# Schematic.net
KiCad netlist of a schematic drawn in Altium Designer
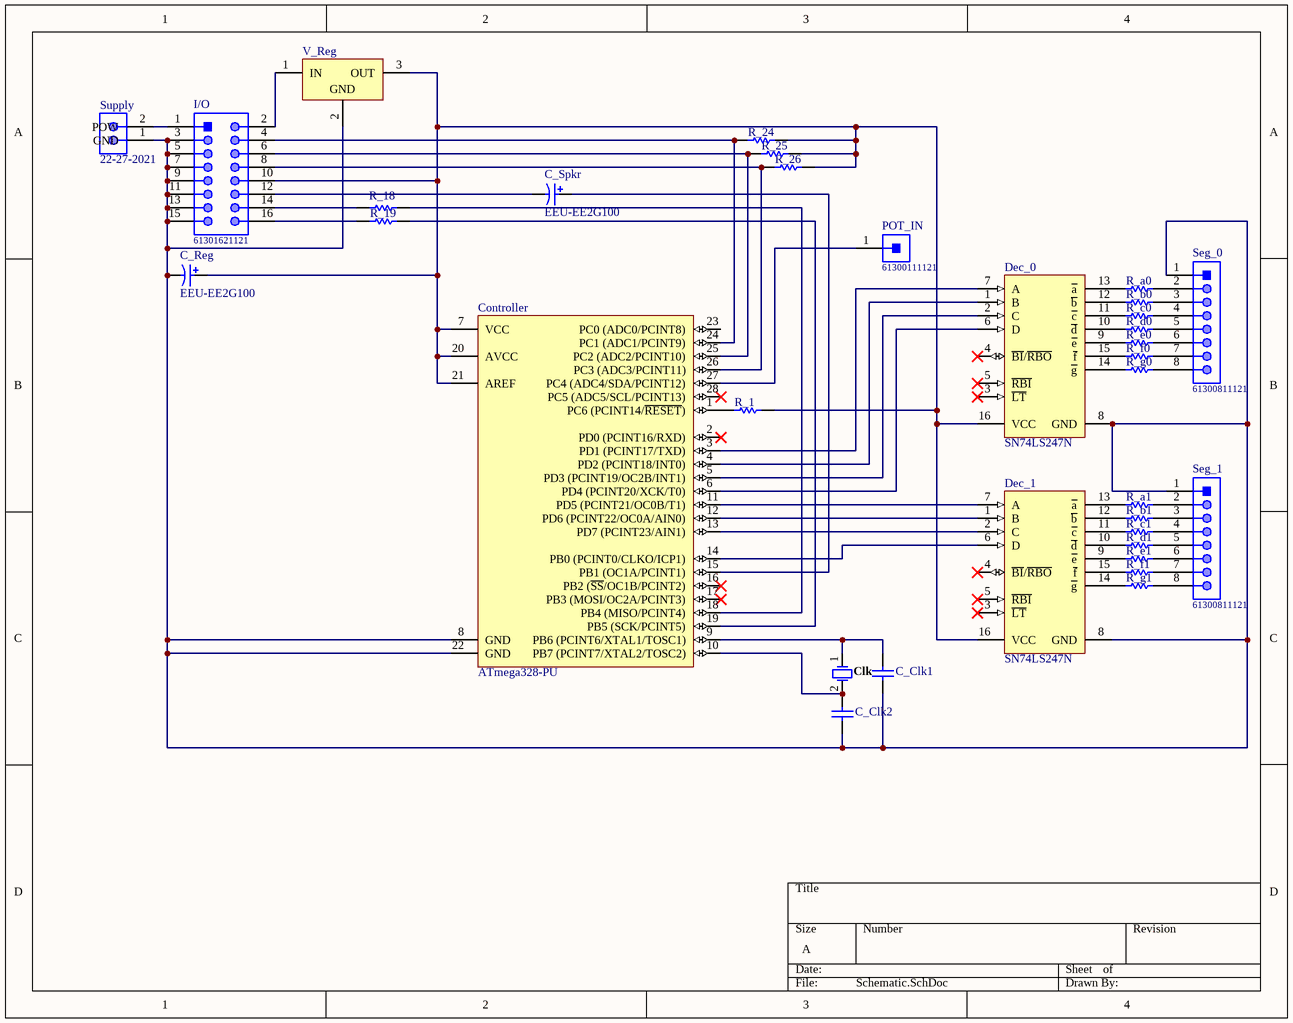
[diagram p0: Schematic.SchDoc]

(export (version "E")
  (design (tool "Eeschema 10.0.6"))
  (components
    (comp (ref "Clk")
      (value "FOXSLF/120-20")
      (footprint "FOX-FOXSLF-2_V")
      (description "Resistance Weld Thru-Hole Crystal, 12 MHz, +/-30 ppm, -20 to 70 degC, 2-Pin THD, RoHS, Bulk")
      (libsource (lib "Altium Content Vault") (part "XTAL-1-2-2"))
    )
    (comp (ref "Controller")
      (value "ATmega328-PU")
      (footprint "28P3")
      (libsource (lib "Altium Content Vault") (part "MC-8B-ATM48-IL28"))
    )
    (comp (ref "C_Clk1")
      (value "C315C220K1G5TA")
      (footprint "KEMT-C315-THT-2")
      (description "Capacitor, Ceramic, 22 pF, +/-10 %, 100 V, -55 to 125 degC, 2-Pin THD, RoHS, Bulk")
      (libsource (lib "Altium Content Vault") (part "CAP-NP-2"))
    )
    (comp (ref "C_Clk2")
      (value "C315C220K1G5TA")
      (footprint "KEMT-C315-THT-2")
      (description "Capacitor, Ceramic, 22 pF, +/-10 %, 100 V, -55 to 125 degC, 2-Pin THD, RoHS, Bulk")
      (libsource (lib "Altium Content Vault") (part "CAP-NP-2"))
    )
    (comp (ref "C_Reg")
      (value "EEU-EE2G100")
      (footprint "PNSC-EEU-EE2G100-2_V")
      (fields (field (name "MANUFACTURER") "Panasonic"))
      (libsource (lib "Altium Content Vault") (part "PNSC-CAP-P-2"))
    )
    (comp (ref "C_Spkr")
      (value "EEU-EE2G100")
      (footprint "PNSC-EEU-EE2G100-2_V")
      (fields (field (name "MANUFACTURER") "Panasonic"))
      (libsource (lib "Altium Content Vault") (part "PNSC-CAP-P-2"))
    )
    (comp (ref "Dec_0")
      (value "SN74LS247N")
      (footprint "N0016A")
      (description "BCD-to-7-Segment Decoder / Driver, 4.75 to 5.25 V, 0 to 70 degC, 16-pin DIP (N16), Pb-Free (RoHS)")
      (fields (field (name "MANUFACTURER") "Texas Instruments"))
      (libsource (lib "Altium Content Vault") (part "TI-SNX4XX247-16"))
    )
    (comp (ref "Dec_1")
      (value "SN74LS247N")
      (footprint "N0016A")
      (description "BCD-to-7-Segment Decoder / Driver, 4.75 to 5.25 V, 0 to 70 degC, 16-pin DIP (N16), Pb-Free (RoHS)")
      (fields (field (name "MANUFACTURER") "Texas Instruments"))
      (libsource (lib "Altium Content Vault") (part "TI-SNX4XX247-16"))
    )
    (comp (ref "I/O")
      (value "61301621121")
      (footprint "61301621121")
      (description "THT Vertical Pin Header WR-PHD, Pitch 2.54 mm, Dual Row, 16 pins")
      (fields (field (name "MANUFACTURER") "Wurth Elektronik") (field (name "PUBLISHER") "WurthElektronik"))
      (libsource (lib "Altium Content Vault") (part "WE-CN-2P-M-R16"))
    )
    (comp (ref "POT_IN")
      (value "61300111121")
      (footprint "61300111121")
      (description "THT Vertical Pin Header WR-PHD, Pitch 2.54 mm, Single Row, 1 pins")
      (fields (field (name "MANUFACTURER") "Wurth Elektronik") (field (name "PUBLISHER") "WurthElektronik"))
      (libsource (lib "Altium Content Vault") (part "WE-CN-1P-M-R1"))
    )
    (comp (ref "R_1")
      (value "MFR-25FBF52-1K")
      (footprint "RESA60-630X240")
      (description "Axial Resistor, 1 KOhm, +/- 1%, 250 mW, -55 to 155 degC, 2-Pin THD, RoHS, Bulk")
      (fields (field (name "TOLERANCE") "1%"))
      (libsource (lib "Altium Content Vault") (part "RES-2"))
    )
    (comp (ref "R_18")
      (value "FR-25FF52-1K")
      (footprint "RESA60-630X240")
      (description "Axial Resistor, 1 KOhm, +/- 1%, 250 mW, -55 to 155 degC, 2-Pin THD, RoHS, Bulk")
      (fields (field (name "TOLERANCE") "1%"))
      (libsource (lib "Altium Content Vault") (part "RES-2"))
    )
    (comp (ref "R_19")
      (value "MFR-25FBF52-1K")
      (footprint "RESA60-630X240")
      (description "Axial Resistor, 1 KOhm, +/- 1%, 250 mW, -55 to 155 degC, 2-Pin THD, RoHS, Bulk")
      (fields (field (name "TOLERANCE") "1%"))
      (libsource (lib "Altium Content Vault") (part "RES-2"))
    )
    (comp (ref "R_24")
      (value "MFR-25FBF52-1K")
      (footprint "RESA60-630X240")
      (description "Axial Resistor, 1 KOhm, +/- 1%, 250 mW, -55 to 155 degC, 2-Pin THD, RoHS, Bulk")
      (fields (field (name "TOLERANCE") "1%"))
      (libsource (lib "Altium Content Vault") (part "RES-2"))
    )
    (comp (ref "R_25")
      (value "MFR-25FBF52-1K")
      (footprint "RESA60-630X240")
      (description "Axial Resistor, 1 KOhm, +/- 1%, 250 mW, -55 to 155 degC, 2-Pin THD, RoHS, Bulk")
      (fields (field (name "TOLERANCE") "1%"))
      (libsource (lib "Altium Content Vault") (part "RES-2"))
    )
    (comp (ref "R_26")
      (value "MFR-25FBF52-1K")
      (footprint "RESA60-630X240")
      (description "Axial Resistor, 1 KOhm, +/- 1%, 250 mW, -55 to 155 degC, 2-Pin THD, RoHS, Bulk")
      (fields (field (name "TOLERANCE") "1%"))
      (libsource (lib "Altium Content Vault") (part "RES-2"))
    )
    (comp (ref "R_a0")
      (value "MFR-25FBF52-1K")
      (footprint "RESA60-630X240")
      (description "Axial Resistor, 1 KOhm, +/- 1%, 250 mW, -55 to 155 degC, 2-Pin THD, RoHS, Bulk")
      (fields (field (name "TOLERANCE") "1%"))
      (libsource (lib "Altium Content Vault") (part "RES-2"))
    )
    (comp (ref "R_a1")
      (value "MFR-25FBF52-1K")
      (footprint "RESA60-630X240")
      (description "Axial Resistor, 1 KOhm, +/- 1%, 250 mW, -55 to 155 degC, 2-Pin THD, RoHS, Bulk")
      (fields (field (name "TOLERANCE") "1%"))
      (libsource (lib "Altium Content Vault") (part "RES-2"))
    )
    (comp (ref "R_b0")
      (value "MFR-25FBF52-1K")
      (footprint "RESA60-630X240")
      (description "Axial Resistor, 1 KOhm, +/- 1%, 250 mW, -55 to 155 degC, 2-Pin THD, RoHS, Bulk")
      (fields (field (name "TOLERANCE") "1%"))
      (libsource (lib "Altium Content Vault") (part "RES-2"))
    )
    (comp (ref "R_b1")
      (value "MFR-25FBF52-1K")
      (footprint "RESA60-630X240")
      (description "Axial Resistor, 1 KOhm, +/- 1%, 250 mW, -55 to 155 degC, 2-Pin THD, RoHS, Bulk")
      (fields (field (name "TOLERANCE") "1%"))
      (libsource (lib "Altium Content Vault") (part "RES-2"))
    )
    (comp (ref "R_c0")
      (value "MFR-25FBF52-1K")
      (footprint "RESA60-630X240")
      (description "Axial Resistor, 1 KOhm, +/- 1%, 250 mW, -55 to 155 degC, 2-Pin THD, RoHS, Bulk")
      (fields (field (name "TOLERANCE") "1%"))
      (libsource (lib "Altium Content Vault") (part "RES-2"))
    )
    (comp (ref "R_c1")
      (value "MFR-25FBF52-1K")
      (footprint "RESA60-630X240")
      (description "Axial Resistor, 1 KOhm, +/- 1%, 250 mW, -55 to 155 degC, 2-Pin THD, RoHS, Bulk")
      (fields (field (name "TOLERANCE") "1%"))
      (libsource (lib "Altium Content Vault") (part "RES-2"))
    )
    (comp (ref "R_d0")
      (value "MFR-25FBF52-1K")
      (footprint "RESA60-630X240")
      (description "Axial Resistor, 1 KOhm, +/- 1%, 250 mW, -55 to 155 degC, 2-Pin THD, RoHS, Bulk")
      (fields (field (name "TOLERANCE") "1%"))
      (libsource (lib "Altium Content Vault") (part "RES-2"))
    )
    (comp (ref "R_d1")
      (value "MFR-25FBF52-1K")
      (footprint "RESA60-630X240")
      (description "Axial Resistor, 1 KOhm, +/- 1%, 250 mW, -55 to 155 degC, 2-Pin THD, RoHS, Bulk")
      (fields (field (name "TOLERANCE") "1%"))
      (libsource (lib "Altium Content Vault") (part "RES-2"))
    )
    (comp (ref "R_e0")
      (value "MFR-25FBF52-1K")
      (footprint "RESA60-630X240")
      (description "Axial Resistor, 1 KOhm, +/- 1%, 250 mW, -55 to 155 degC, 2-Pin THD, RoHS, Bulk")
      (fields (field (name "TOLERANCE") "1%"))
      (libsource (lib "Altium Content Vault") (part "RES-2"))
    )
    (comp (ref "R_e1")
      (value "MFR-25FBF52-1K")
      (footprint "RESA60-630X240")
      (description "Axial Resistor, 1 KOhm, +/- 1%, 250 mW, -55 to 155 degC, 2-Pin THD, RoHS, Bulk")
      (fields (field (name "TOLERANCE") "1%"))
      (libsource (lib "Altium Content Vault") (part "RES-2"))
    )
    (comp (ref "R_f0")
      (value "MFR-25FBF52-1K")
      (footprint "RESA60-630X240")
      (description "Axial Resistor, 1 KOhm, +/- 1%, 250 mW, -55 to 155 degC, 2-Pin THD, RoHS, Bulk")
      (fields (field (name "TOLERANCE") "1%"))
      (libsource (lib "Altium Content Vault") (part "RES-2"))
    )
    (comp (ref "R_f1")
      (value "MFR-25FBF52-1K")
      (footprint "RESA60-630X240")
      (description "Axial Resistor, 1 KOhm, +/- 1%, 250 mW, -55 to 155 degC, 2-Pin THD, RoHS, Bulk")
      (fields (field (name "TOLERANCE") "1%"))
      (libsource (lib "Altium Content Vault") (part "RES-2"))
    )
    (comp (ref "R_g0")
      (value "MFR-25FBF52-1K")
      (footprint "RESA60-630X240")
      (description "Axial Resistor, 1 KOhm, +/- 1%, 250 mW, -55 to 155 degC, 2-Pin THD, RoHS, Bulk")
      (fields (field (name "TOLERANCE") "1%"))
      (libsource (lib "Altium Content Vault") (part "RES-2"))
    )
    (comp (ref "R_g1")
      (value "MFR-25FBF52-1K")
      (footprint "RESA60-630X240")
      (description "Axial Resistor, 1 KOhm, +/- 1%, 250 mW, -55 to 155 degC, 2-Pin THD, RoHS, Bulk")
      (fields (field (name "TOLERANCE") "1%"))
      (libsource (lib "Altium Content Vault") (part "RES-2"))
    )
    (comp (ref "Seg_0")
      (value "61300811121")
      (footprint "61300811121")
      (description "THT Vertical Pin Header WR-PHD, Pitch 2.54 mm, Single Row, 8 pins")
      (fields (field (name "MANUFACTURER") "Wurth Elektronik") (field (name "PUBLISHER") "WurthElektronik"))
      (libsource (lib "Altium Content Vault") (part "WE-CN-1P-M-R8"))
    )
    (comp (ref "Seg_1")
      (value "61300811121")
      (footprint "61300811121")
      (description "THT Vertical Pin Header WR-PHD, Pitch 2.54 mm, Single Row, 8 pins")
      (fields (field (name "MANUFACTURER") "Wurth Elektronik") (field (name "PUBLISHER") "WurthElektronik"))
      (libsource (lib "Altium Content Vault") (part "WE-CN-1P-M-R8"))
    )
    (comp (ref "Supply")
      (value "22-27-2021")
      (footprint "MOLX-22-27-2021_V")
      (fields (field (name "MANUFACTURER") "Molex") (field (name "PARTNUMBER") "0022272021"))
      (libsource (lib "Altium Content Vault") (part "CN-1P-M-R2"))
    )
    (comp (ref "V_Reg")
      (value "LM7805CT")
      (footprint "FAIR-TO-220-3")
      (description "Positive Voltage Regulator, 5 V, 1 A, -40 to 125 degC, 3-Pin TO-220, RoHS, Tube")
      (fields (field (name "MANUFACTURER") "FairchildSemiconductor"))
      (libsource (lib "Altium Content Vault") (part "FAIR-LM7805CT-TO220-3"))
    )
  )
  (nets
    (net (code "1") (name "Net-(C_Spkr-Pad2)") (class "Default")
      (node (ref "C_Spkr") (pin "2") (pinfunction "2_2") (pintype "passive"))
      (node (ref "I/O") (pin "12") (pinfunction "12_12") (pintype "passive"))
    )
    (net (code "2") (name "Net-(Controller-AREF)") (class "Default")
      (node (ref "C_Reg") (pin "1") (pinfunction "1_1") (pintype "passive"))
      (node (ref "Controller") (pin "20") (pinfunction "AVCC_20") (pintype "power_in"))
      (node (ref "Controller") (pin "21") (pinfunction "AREF_21") (pintype "power_in"))
      (node (ref "Controller") (pin "7") (pinfunction "VCC_7") (pintype "power_in"))
      (node (ref "Dec_0") (pin "16") (pinfunction "VCC_16") (pintype "power_in"))
      (node (ref "Dec_1") (pin "16") (pinfunction "VCC_16") (pintype "power_in"))
      (node (ref "I/O") (pin "10") (pinfunction "10_10") (pintype "passive"))
      (node (ref "R_1") (pin "2") (pinfunction "2_2") (pintype "passive"))
      (node (ref "R_24") (pin "2") (pinfunction "2_2") (pintype "passive"))
      (node (ref "R_25") (pin "2") (pinfunction "2_2") (pintype "passive"))
      (node (ref "R_26") (pin "2") (pinfunction "2_2") (pintype "passive"))
      (node (ref "V_Reg") (pin "3") (pinfunction "OUT_3") (pintype "power_in"))
    )
    (net (code "3") (name "Net-(Controller-PB0_(PCINT0{slash}CLKO{slash}ICP1))") (class "Default")
      (node (ref "Controller") (pin "14") (pinfunction "PB0_(PCINT0/CLKO/ICP1)_14") (pintype "bidirectional"))
      (node (ref "Dec_1") (pin "6") (pinfunction "D_6") (pintype "input"))
    )
    (net (code "4") (name "Net-(Controller-PB1_(OC1A{slash}PCINT1))") (class "Default")
      (node (ref "C_Spkr") (pin "1") (pinfunction "1_1") (pintype "passive"))
      (node (ref "Controller") (pin "15") (pinfunction "PB1_(OC1A/PCINT1)_15") (pintype "bidirectional"))
    )
    (net (code "5") (name "Net-(Controller-PB4_(MISO{slash}PCINT4))") (class "Default")
      (node (ref "Controller") (pin "18") (pinfunction "PB4_(MISO/PCINT4)_18") (pintype "bidirectional"))
      (node (ref "R_18") (pin "2") (pinfunction "2_2") (pintype "passive"))
    )
    (net (code "6") (name "Net-(Controller-PB5_(SCK{slash}PCINT5))") (class "Default")
      (node (ref "Controller") (pin "19") (pinfunction "PB5_(SCK/PCINT5)_19") (pintype "bidirectional"))
      (node (ref "R_19") (pin "2") (pinfunction "2_2") (pintype "passive"))
    )
    (net (code "7") (name "Net-(Controller-PB6_(PCINT6{slash}XTAL1{slash}TOSC1))") (class "Default")
      (node (ref "C_Clk1") (pin "2") (pinfunction "2_2") (pintype "passive"))
      (node (ref "Clk") (pin "1") (pinfunction "1_1") (pintype "passive"))
      (node (ref "Controller") (pin "9") (pinfunction "PB6_(PCINT6/XTAL1/TOSC1)_9") (pintype "bidirectional"))
    )
    (net (code "8") (name "Net-(Controller-PB7_(PCINT7{slash}XTAL2{slash}TOSC2))") (class "Default")
      (node (ref "C_Clk2") (pin "1") (pinfunction "1_1") (pintype "passive"))
      (node (ref "Clk") (pin "2") (pinfunction "2_2") (pintype "passive"))
      (node (ref "Controller") (pin "10") (pinfunction "PB7_(PCINT7/XTAL2/TOSC2)_10") (pintype "bidirectional"))
    )
    (net (code "9") (name "Net-(Controller-PC1_(ADC1{slash}PCINT9))") (class "Default")
      (node (ref "Controller") (pin "24") (pinfunction "PC1_(ADC1/PCINT9)_24") (pintype "bidirectional"))
      (node (ref "I/O") (pin "4") (pinfunction "4_4") (pintype "passive"))
      (node (ref "R_24") (pin "1") (pinfunction "1_1") (pintype "passive"))
    )
    (net (code "10") (name "Net-(Controller-PC2_(ADC2{slash}PCINT10))") (class "Default")
      (node (ref "Controller") (pin "25") (pinfunction "PC2_(ADC2/PCINT10)_25") (pintype "bidirectional"))
      (node (ref "I/O") (pin "6") (pinfunction "6_6") (pintype "passive"))
      (node (ref "R_25") (pin "1") (pinfunction "1_1") (pintype "passive"))
    )
    (net (code "11") (name "Net-(Controller-PC3_(ADC3{slash}PCINT11))") (class "Default")
      (node (ref "Controller") (pin "26") (pinfunction "PC3_(ADC3/PCINT11)_26") (pintype "bidirectional"))
      (node (ref "I/O") (pin "8") (pinfunction "8_8") (pintype "passive"))
      (node (ref "R_26") (pin "1") (pinfunction "1_1") (pintype "passive"))
    )
    (net (code "12") (name "Net-(Controller-PC4_(ADC4{slash}SDA{slash}PCINT12))") (class "Default")
      (node (ref "Controller") (pin "27") (pinfunction "PC4_(ADC4/SDA/PCINT12)_27") (pintype "bidirectional"))
      (node (ref "POT_IN") (pin "1") (pinfunction "1_1") (pintype "passive"))
    )
    (net (code "13") (name "Net-(Controller-PC6_(PCINT14{slash}~{RESET}))") (class "Default")
      (node (ref "Controller") (pin "1") (pinfunction "PC6_(PCINT14/~{RESET})_1") (pintype "bidirectional"))
      (node (ref "R_1") (pin "1") (pinfunction "1_1") (pintype "passive"))
    )
    (net (code "14") (name "Net-(Controller-PD1_(PCINT17{slash}TXD))") (class "Default")
      (node (ref "Controller") (pin "3") (pinfunction "PD1_(PCINT17/TXD)_3") (pintype "bidirectional"))
      (node (ref "Dec_0") (pin "7") (pinfunction "A_7") (pintype "input"))
    )
    (net (code "15") (name "Net-(Controller-PD2_(PCINT18{slash}INT0))") (class "Default")
      (node (ref "Controller") (pin "4") (pinfunction "PD2_(PCINT18/INT0)_4") (pintype "bidirectional"))
      (node (ref "Dec_0") (pin "1") (pinfunction "B_1") (pintype "input"))
    )
    (net (code "16") (name "Net-(Controller-PD3_(PCINT19{slash}OC2B{slash}INT1))") (class "Default")
      (node (ref "Controller") (pin "5") (pinfunction "PD3_(PCINT19/OC2B/INT1)_5") (pintype "bidirectional"))
      (node (ref "Dec_0") (pin "2") (pinfunction "C_2") (pintype "input"))
    )
    (net (code "17") (name "Net-(Controller-PD4_(PCINT20{slash}XCK{slash}T0))") (class "Default")
      (node (ref "Controller") (pin "6") (pinfunction "PD4_(PCINT20/XCK/T0)_6") (pintype "bidirectional"))
      (node (ref "Dec_0") (pin "6") (pinfunction "D_6") (pintype "input"))
    )
    (net (code "18") (name "Net-(Controller-PD5_(PCINT21{slash}OC0B{slash}T1))") (class "Default")
      (node (ref "Controller") (pin "11") (pinfunction "PD5_(PCINT21/OC0B/T1)_11") (pintype "bidirectional"))
      (node (ref "Dec_1") (pin "7") (pinfunction "A_7") (pintype "input"))
    )
    (net (code "19") (name "Net-(Controller-PD6_(PCINT22{slash}OC0A{slash}AIN0))") (class "Default")
      (node (ref "Controller") (pin "12") (pinfunction "PD6_(PCINT22/OC0A/AIN0)_12") (pintype "bidirectional"))
      (node (ref "Dec_1") (pin "1") (pinfunction "B_1") (pintype "input"))
    )
    (net (code "20") (name "Net-(Controller-PD7_(PCINT23{slash}AIN1))") (class "Default")
      (node (ref "Controller") (pin "13") (pinfunction "PD7_(PCINT23/AIN1)_13") (pintype "bidirectional"))
      (node (ref "Dec_1") (pin "2") (pinfunction "C_2") (pintype "input"))
    )
    (net (code "21") (name "Net-(Dec_0-GND)") (class "Default")
      (node (ref "C_Clk1") (pin "1") (pinfunction "1_1") (pintype "passive"))
      (node (ref "C_Clk2") (pin "2") (pinfunction "2_2") (pintype "passive"))
      (node (ref "C_Reg") (pin "2") (pinfunction "2_2") (pintype "passive"))
      (node (ref "Controller") (pin "22") (pinfunction "GND_22") (pintype "power_in"))
      (node (ref "Controller") (pin "8") (pinfunction "GND_8") (pintype "power_in"))
      (node (ref "Dec_0") (pin "8") (pinfunction "GND_8") (pintype "power_in"))
      (node (ref "Dec_1") (pin "8") (pinfunction "GND_8") (pintype "power_in"))
      (node (ref "I/O") (pin "11") (pinfunction "11_11") (pintype "passive"))
      (node (ref "I/O") (pin "13") (pinfunction "13_13") (pintype "passive"))
      (node (ref "I/O") (pin "15") (pinfunction "15_15") (pintype "passive"))
      (node (ref "I/O") (pin "3") (pinfunction "3_3") (pintype "passive"))
      (node (ref "I/O") (pin "5") (pinfunction "5_5") (pintype "passive"))
      (node (ref "I/O") (pin "7") (pinfunction "7_7") (pintype "passive"))
      (node (ref "I/O") (pin "9") (pinfunction "9_9") (pintype "passive"))
      (node (ref "Seg_0") (pin "1") (pinfunction "1_1") (pintype "passive"))
      (node (ref "Seg_1") (pin "1") (pinfunction "1_1") (pintype "passive"))
      (node (ref "Supply") (pin "1") (pinfunction "GND_1") (pintype "passive"))
      (node (ref "V_Reg") (pin "2") (pinfunction "GND_2") (pintype "power_in"))
    )
    (net (code "22") (name "Net-(Dec_0-~{a})") (class "Default")
      (node (ref "Dec_0") (pin "13") (pinfunction "~{a}_13") (pintype "open_collector"))
      (node (ref "R_a0") (pin "1") (pinfunction "1_1") (pintype "passive"))
    )
    (net (code "23") (name "Net-(Dec_0-~{b})") (class "Default")
      (node (ref "Dec_0") (pin "12") (pinfunction "~{b}_12") (pintype "open_collector"))
      (node (ref "R_b0") (pin "1") (pinfunction "1_1") (pintype "passive"))
    )
    (net (code "24") (name "Net-(Dec_0-~{c})") (class "Default")
      (node (ref "Dec_0") (pin "11") (pinfunction "~{c}_11") (pintype "open_collector"))
      (node (ref "R_c0") (pin "1") (pinfunction "1_1") (pintype "passive"))
    )
    (net (code "25") (name "Net-(Dec_0-~{d})") (class "Default")
      (node (ref "Dec_0") (pin "10") (pinfunction "~{d}_10") (pintype "open_collector"))
      (node (ref "R_d0") (pin "1") (pinfunction "1_1") (pintype "passive"))
    )
    (net (code "26") (name "Net-(Dec_0-~{e})") (class "Default")
      (node (ref "Dec_0") (pin "9") (pinfunction "~{e}_9") (pintype "open_collector"))
      (node (ref "R_e0") (pin "1") (pinfunction "1_1") (pintype "passive"))
    )
    (net (code "27") (name "Net-(Dec_0-~{f})") (class "Default")
      (node (ref "Dec_0") (pin "15") (pinfunction "~{f}_15") (pintype "open_collector"))
      (node (ref "R_f0") (pin "1") (pinfunction "1_1") (pintype "passive"))
    )
    (net (code "28") (name "Net-(Dec_0-~{g})") (class "Default")
      (node (ref "Dec_0") (pin "14") (pinfunction "~{g}_14") (pintype "open_collector"))
      (node (ref "R_g0") (pin "1") (pinfunction "1_1") (pintype "passive"))
    )
    (net (code "29") (name "Net-(Dec_1-~{a})") (class "Default")
      (node (ref "Dec_1") (pin "13") (pinfunction "~{a}_13") (pintype "open_collector"))
      (node (ref "R_a1") (pin "1") (pinfunction "1_1") (pintype "passive"))
    )
    (net (code "30") (name "Net-(Dec_1-~{b})") (class "Default")
      (node (ref "Dec_1") (pin "12") (pinfunction "~{b}_12") (pintype "open_collector"))
      (node (ref "R_b1") (pin "1") (pinfunction "1_1") (pintype "passive"))
    )
    (net (code "31") (name "Net-(Dec_1-~{c})") (class "Default")
      (node (ref "Dec_1") (pin "11") (pinfunction "~{c}_11") (pintype "open_collector"))
      (node (ref "R_c1") (pin "1") (pinfunction "1_1") (pintype "passive"))
    )
    (net (code "32") (name "Net-(Dec_1-~{d})") (class "Default")
      (node (ref "Dec_1") (pin "10") (pinfunction "~{d}_10") (pintype "open_collector"))
      (node (ref "R_d1") (pin "1") (pinfunction "1_1") (pintype "passive"))
    )
    (net (code "33") (name "Net-(Dec_1-~{e})") (class "Default")
      (node (ref "Dec_1") (pin "9") (pinfunction "~{e}_9") (pintype "open_collector"))
      (node (ref "R_e1") (pin "1") (pinfunction "1_1") (pintype "passive"))
    )
    (net (code "34") (name "Net-(Dec_1-~{f})") (class "Default")
      (node (ref "Dec_1") (pin "15") (pinfunction "~{f}_15") (pintype "open_collector"))
      (node (ref "R_f1") (pin "1") (pinfunction "1_1") (pintype "passive"))
    )
    (net (code "35") (name "Net-(Dec_1-~{g})") (class "Default")
      (node (ref "Dec_1") (pin "14") (pinfunction "~{g}_14") (pintype "open_collector"))
      (node (ref "R_g1") (pin "1") (pinfunction "1_1") (pintype "passive"))
    )
    (net (code "36") (name "Net-(I/O-Pad14)") (class "Default")
      (node (ref "I/O") (pin "14") (pinfunction "14_14") (pintype "passive"))
      (node (ref "R_18") (pin "1") (pinfunction "1_1") (pintype "passive"))
    )
    (net (code "37") (name "Net-(I/O-Pad16)") (class "Default")
      (node (ref "I/O") (pin "16") (pinfunction "16_16") (pintype "passive"))
      (node (ref "R_19") (pin "1") (pinfunction "1_1") (pintype "passive"))
    )
    (net (code "38") (name "Net-(R_a0-Pad2)") (class "Default")
      (node (ref "R_a0") (pin "2") (pinfunction "2_2") (pintype "passive"))
      (node (ref "Seg_0") (pin "2") (pinfunction "2_2") (pintype "passive"))
    )
    (net (code "39") (name "Net-(R_a1-Pad2)") (class "Default")
      (node (ref "R_a1") (pin "2") (pinfunction "2_2") (pintype "passive"))
      (node (ref "Seg_1") (pin "2") (pinfunction "2_2") (pintype "passive"))
    )
    (net (code "40") (name "Net-(R_b0-Pad2)") (class "Default")
      (node (ref "R_b0") (pin "2") (pinfunction "2_2") (pintype "passive"))
      (node (ref "Seg_0") (pin "3") (pinfunction "3_3") (pintype "passive"))
    )
    (net (code "41") (name "Net-(R_b1-Pad2)") (class "Default")
      (node (ref "R_b1") (pin "2") (pinfunction "2_2") (pintype "passive"))
      (node (ref "Seg_1") (pin "3") (pinfunction "3_3") (pintype "passive"))
    )
    (net (code "42") (name "Net-(R_c0-Pad2)") (class "Default")
      (node (ref "R_c0") (pin "2") (pinfunction "2_2") (pintype "passive"))
      (node (ref "Seg_0") (pin "4") (pinfunction "4_4") (pintype "passive"))
    )
    (net (code "43") (name "Net-(R_c1-Pad2)") (class "Default")
      (node (ref "R_c1") (pin "2") (pinfunction "2_2") (pintype "passive"))
      (node (ref "Seg_1") (pin "4") (pinfunction "4_4") (pintype "passive"))
    )
    (net (code "44") (name "Net-(R_d0-Pad2)") (class "Default")
      (node (ref "R_d0") (pin "2") (pinfunction "2_2") (pintype "passive"))
      (node (ref "Seg_0") (pin "5") (pinfunction "5_5") (pintype "passive"))
    )
    (net (code "45") (name "Net-(R_d1-Pad2)") (class "Default")
      (node (ref "R_d1") (pin "2") (pinfunction "2_2") (pintype "passive"))
      (node (ref "Seg_1") (pin "5") (pinfunction "5_5") (pintype "passive"))
    )
    (net (code "46") (name "Net-(R_e0-Pad2)") (class "Default")
      (node (ref "R_e0") (pin "2") (pinfunction "2_2") (pintype "passive"))
      (node (ref "Seg_0") (pin "6") (pinfunction "6_6") (pintype "passive"))
    )
    (net (code "47") (name "Net-(R_e1-Pad2)") (class "Default")
      (node (ref "R_e1") (pin "2") (pinfunction "2_2") (pintype "passive"))
      (node (ref "Seg_1") (pin "6") (pinfunction "6_6") (pintype "passive"))
    )
    (net (code "48") (name "Net-(R_f0-Pad2)") (class "Default")
      (node (ref "R_f0") (pin "2") (pinfunction "2_2") (pintype "passive"))
      (node (ref "Seg_0") (pin "7") (pinfunction "7_7") (pintype "passive"))
    )
    (net (code "49") (name "Net-(R_f1-Pad2)") (class "Default")
      (node (ref "R_f1") (pin "2") (pinfunction "2_2") (pintype "passive"))
      (node (ref "Seg_1") (pin "7") (pinfunction "7_7") (pintype "passive"))
    )
    (net (code "50") (name "Net-(R_g0-Pad2)") (class "Default")
      (node (ref "R_g0") (pin "2") (pinfunction "2_2") (pintype "passive"))
      (node (ref "Seg_0") (pin "8") (pinfunction "8_8") (pintype "passive"))
    )
    (net (code "51") (name "Net-(R_g1-Pad2)") (class "Default")
      (node (ref "R_g1") (pin "2") (pinfunction "2_2") (pintype "passive"))
      (node (ref "Seg_1") (pin "8") (pinfunction "8_8") (pintype "passive"))
    )
    (net (code "52") (name "Net-(Supply-POW)") (class "Default")
      (node (ref "I/O") (pin "1") (pinfunction "1_1") (pintype "passive"))
      (node (ref "Supply") (pin "2") (pinfunction "POW_2") (pintype "passive"))
    )
    (net (code "53") (name "Net-(V_Reg-IN)") (class "Default")
      (node (ref "I/O") (pin "2") (pinfunction "2_2") (pintype "passive"))
      (node (ref "V_Reg") (pin "1") (pinfunction "IN_1") (pintype "power_in"))
    )
    (net (code "54") (name "unconnected-(Controller-PB2_(~{SS}{slash}OC1B{slash}PCINT2)-Pad16)") (class "Default")
      (node (ref "Controller") (pin "16") (pinfunction "PB2_(~{SS}/OC1B/PCINT2)_16") (pintype "bidirectional+no_connect"))
    )
    (net (code "55") (name "unconnected-(Controller-PB3_(MOSI{slash}OC2A{slash}PCINT3)-Pad17)") (class "Default")
      (node (ref "Controller") (pin "17") (pinfunction "PB3_(MOSI/OC2A/PCINT3)_17") (pintype "bidirectional+no_connect"))
    )
    (net (code "56") (name "unconnected-(Controller-PC0_(ADC0{slash}PCINT8)-Pad23)") (class "Default")
      (node (ref "Controller") (pin "23") (pinfunction "PC0_(ADC0/PCINT8)_23") (pintype "bidirectional"))
    )
    (net (code "57") (name "unconnected-(Controller-PC5_(ADC5{slash}SCL{slash}PCINT13)-Pad28)") (class "Default")
      (node (ref "Controller") (pin "28") (pinfunction "PC5_(ADC5/SCL/PCINT13)_28") (pintype "bidirectional+no_connect"))
    )
    (net (code "58") (name "unconnected-(Controller-PD0_(PCINT16{slash}RXD)-Pad2)") (class "Default")
      (node (ref "Controller") (pin "2") (pinfunction "PD0_(PCINT16/RXD)_2") (pintype "bidirectional+no_connect"))
    )
    (net (code "59") (name "unconnected-(Dec_0-~{BI}{slash}~{RBO}-Pad4)") (class "Default")
      (node (ref "Dec_0") (pin "4") (pinfunction "~{BI}/~{RBO}_4") (pintype "bidirectional+no_connect"))
    )
    (net (code "60") (name "unconnected-(Dec_0-~{LT}-Pad3)") (class "Default")
      (node (ref "Dec_0") (pin "3") (pinfunction "~{LT}_3") (pintype "input+no_connect"))
    )
    (net (code "61") (name "unconnected-(Dec_0-~{RBI}-Pad5)") (class "Default")
      (node (ref "Dec_0") (pin "5") (pinfunction "~{RBI}_5") (pintype "input+no_connect"))
    )
    (net (code "62") (name "unconnected-(Dec_1-~{BI}{slash}~{RBO}-Pad4)") (class "Default")
      (node (ref "Dec_1") (pin "4") (pinfunction "~{BI}/~{RBO}_4") (pintype "bidirectional+no_connect"))
    )
    (net (code "63") (name "unconnected-(Dec_1-~{LT}-Pad3)") (class "Default")
      (node (ref "Dec_1") (pin "3") (pinfunction "~{LT}_3") (pintype "input+no_connect"))
    )
    (net (code "64") (name "unconnected-(Dec_1-~{RBI}-Pad5)") (class "Default")
      (node (ref "Dec_1") (pin "5") (pinfunction "~{RBI}_5") (pintype "input+no_connect"))
    )
  )
)
